# 1-Schematic_Lauflicht_28.net
KiCad netlist of a schematic drawn in EasyEDA
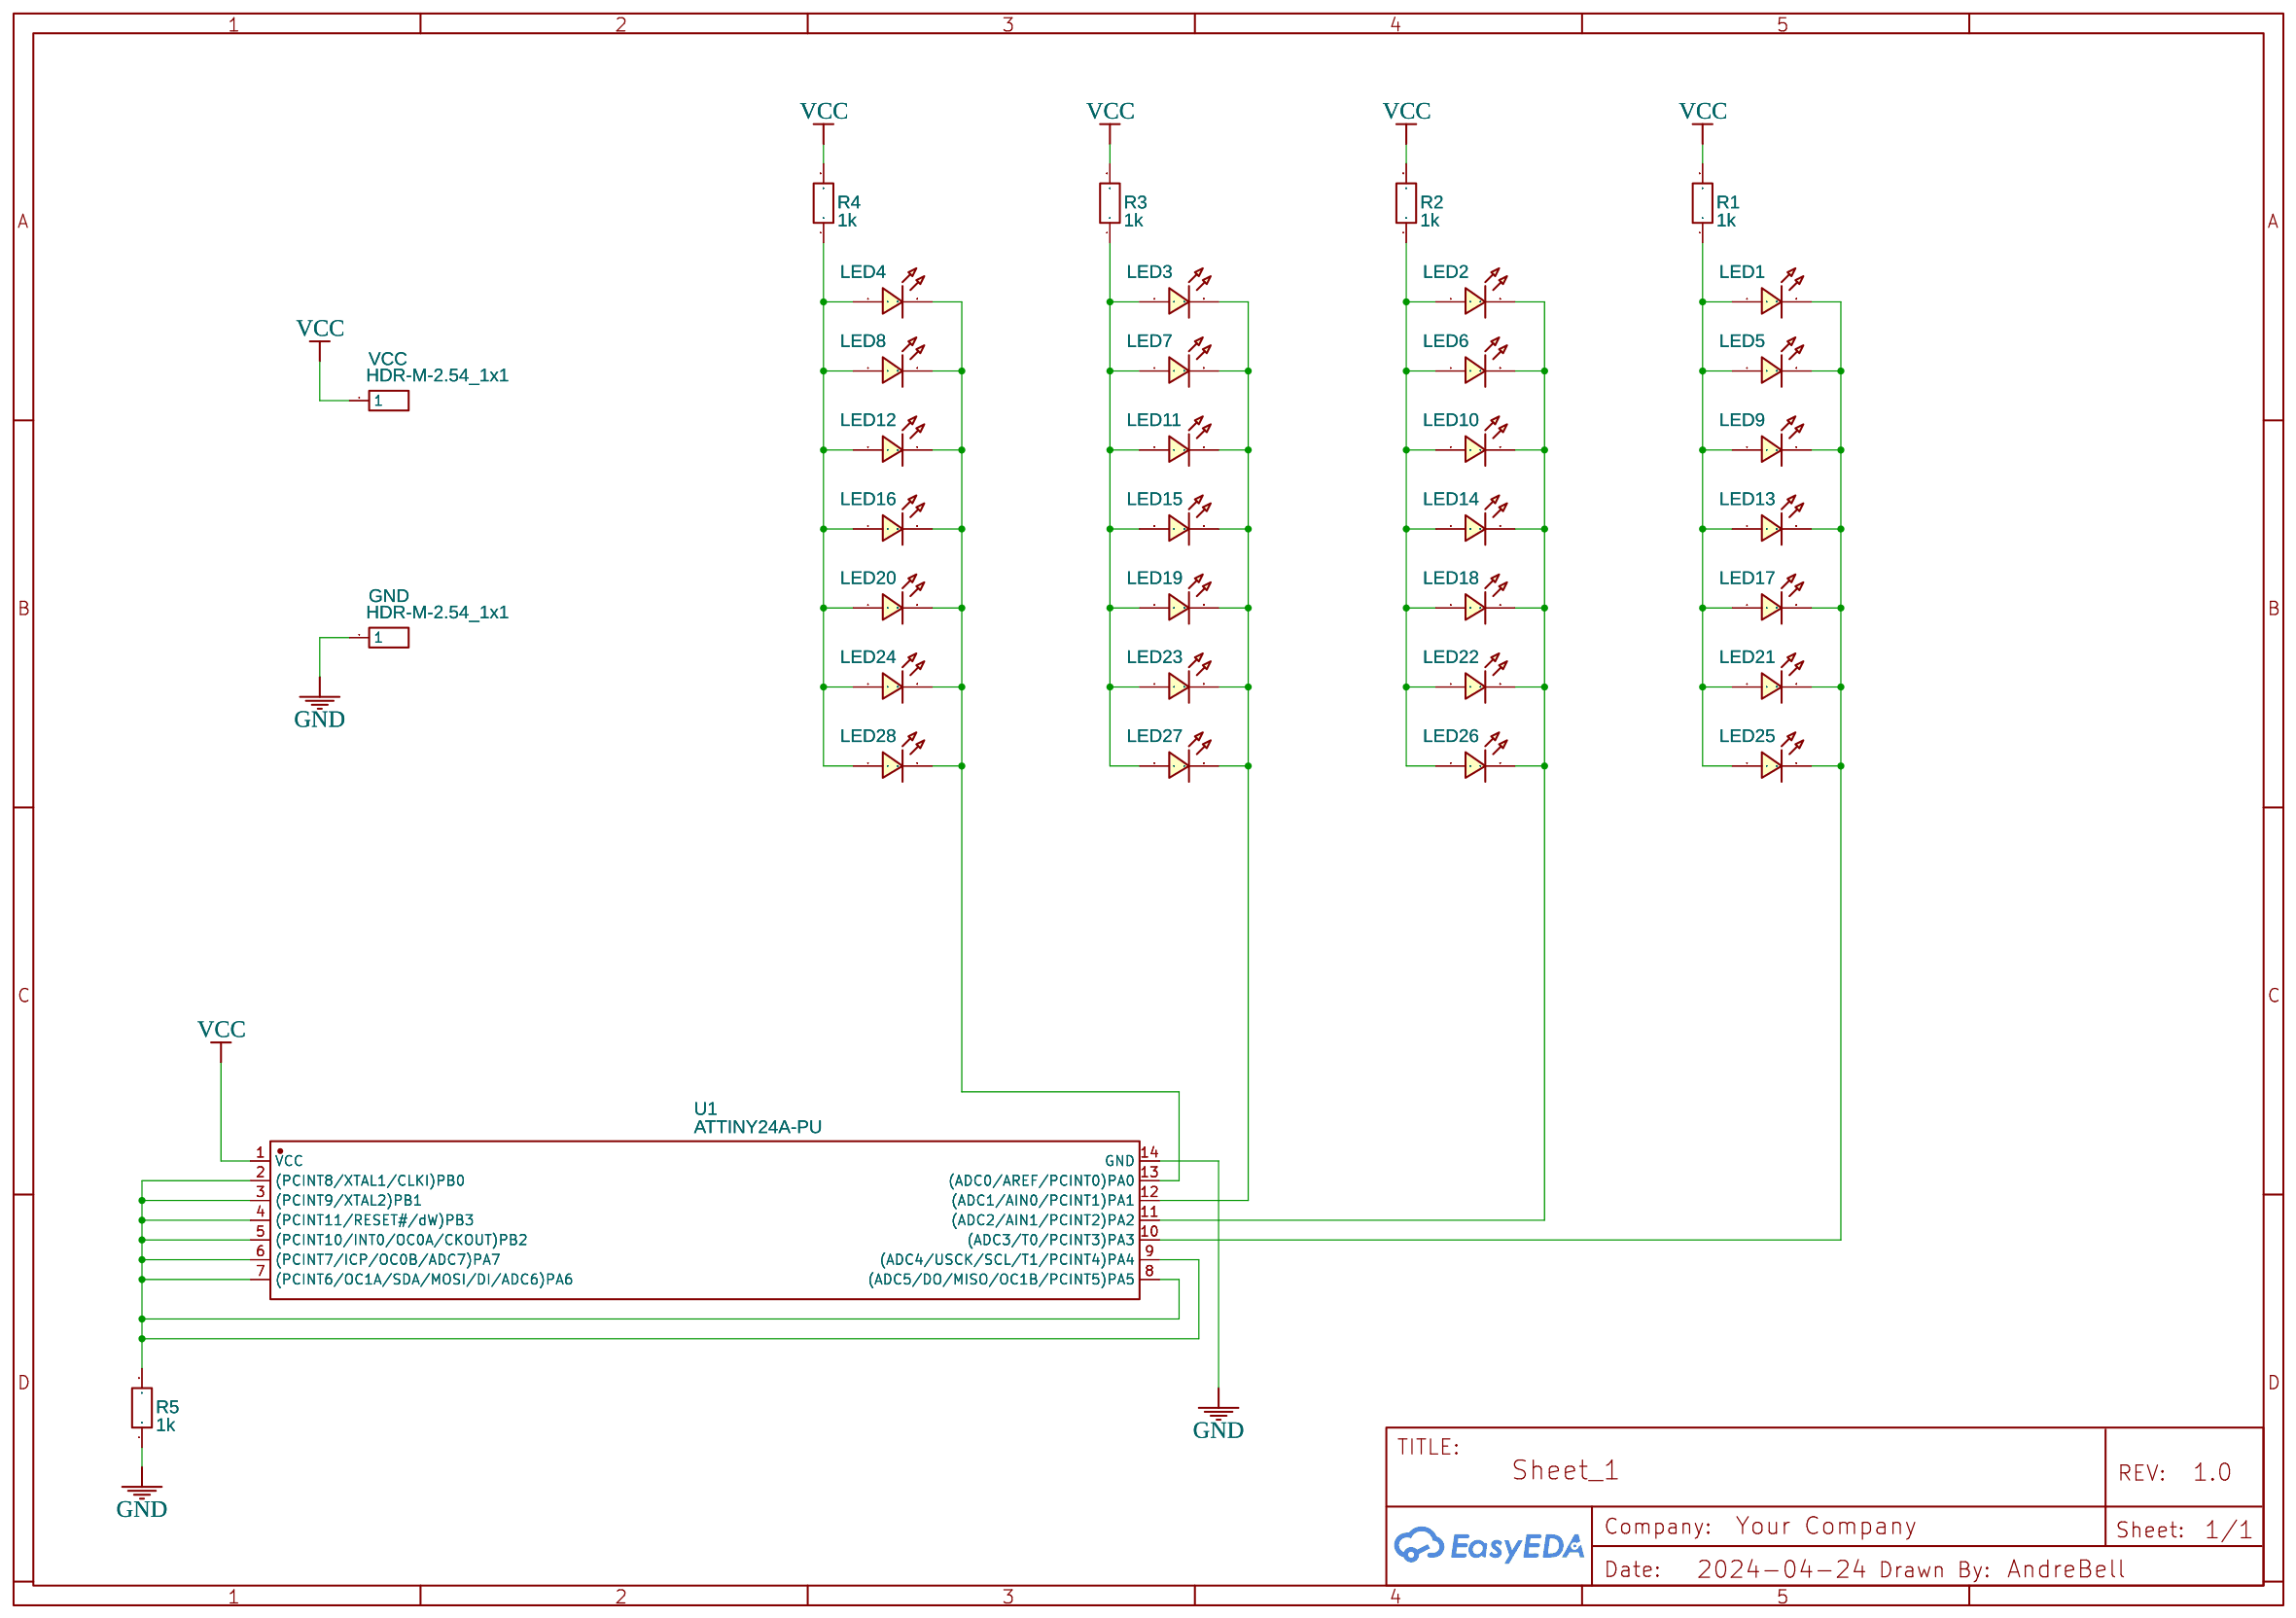
[diagram p0: schematic sheet]

(export (version "E")
  (design (tool "Eeschema 10.0.6"))
  (components
    (comp (ref "GND") (value "HDR-M-2.54_1x1") (libsource (lib "") (part "HDR-M-2.54_1x1_1")))
    (comp (ref "LED1")
      (value "LED-TH-3mm_G")
      (fields
        (field (name "Manufacturer Part") "204-10SYGD/S530-E3")
        (field (name "Manufacturer") "EVERLIGHT(台湾亿光)")
      )
      (libsource (lib "") (part "LED-TH-3mm_G"))
    )
    (comp (ref "LED2")
      (value "LED-TH-3mm_G")
      (fields
        (field (name "Manufacturer Part") "204-10SYGD/S530-E3")
        (field (name "Manufacturer") "EVERLIGHT(台湾亿光)")
      )
      (libsource (lib "") (part "LED-TH-3mm_G"))
    )
    (comp (ref "LED3")
      (value "LED-TH-3mm_G")
      (fields
        (field (name "Manufacturer Part") "204-10SYGD/S530-E3")
        (field (name "Manufacturer") "EVERLIGHT(台湾亿光)")
      )
      (libsource (lib "") (part "LED-TH-3mm_G"))
    )
    (comp (ref "LED4")
      (value "LED-TH-3mm_G")
      (fields
        (field (name "Manufacturer Part") "204-10SYGD/S530-E3")
        (field (name "Manufacturer") "EVERLIGHT(台湾亿光)")
      )
      (libsource (lib "") (part "LED-TH-3mm_G"))
    )
    (comp (ref "LED5")
      (value "LED-TH-3mm_G")
      (fields
        (field (name "Manufacturer Part") "204-10SYGD/S530-E3")
        (field (name "Manufacturer") "EVERLIGHT(台湾亿光)")
      )
      (libsource (lib "") (part "LED-TH-3mm_G"))
    )
    (comp (ref "LED6")
      (value "LED-TH-3mm_G")
      (fields
        (field (name "Manufacturer Part") "204-10SYGD/S530-E3")
        (field (name "Manufacturer") "EVERLIGHT(台湾亿光)")
      )
      (libsource (lib "") (part "LED-TH-3mm_G"))
    )
    (comp (ref "LED7")
      (value "LED-TH-3mm_G")
      (fields
        (field (name "Manufacturer Part") "204-10SYGD/S530-E3")
        (field (name "Manufacturer") "EVERLIGHT(台湾亿光)")
      )
      (libsource (lib "") (part "LED-TH-3mm_G"))
    )
    (comp (ref "LED8")
      (value "LED-TH-3mm_G")
      (fields
        (field (name "Manufacturer Part") "204-10SYGD/S530-E3")
        (field (name "Manufacturer") "EVERLIGHT(台湾亿光)")
      )
      (libsource (lib "") (part "LED-TH-3mm_G"))
    )
    (comp (ref "LED9")
      (value "LED-TH-3mm_G")
      (fields
        (field (name "Manufacturer Part") "204-10SYGD/S530-E3")
        (field (name "Manufacturer") "EVERLIGHT(台湾亿光)")
      )
      (libsource (lib "") (part "LED-TH-3mm_G"))
    )
    (comp (ref "LED10")
      (value "LED-TH-3mm_G")
      (fields
        (field (name "Manufacturer Part") "204-10SYGD/S530-E3")
        (field (name "Manufacturer") "EVERLIGHT(台湾亿光)")
      )
      (libsource (lib "") (part "LED-TH-3mm_G"))
    )
    (comp (ref "LED11")
      (value "LED-TH-3mm_G")
      (fields
        (field (name "Manufacturer Part") "204-10SYGD/S530-E3")
        (field (name "Manufacturer") "EVERLIGHT(台湾亿光)")
      )
      (libsource (lib "") (part "LED-TH-3mm_G"))
    )
    (comp (ref "LED12")
      (value "LED-TH-3mm_G")
      (fields
        (field (name "Manufacturer Part") "204-10SYGD/S530-E3")
        (field (name "Manufacturer") "EVERLIGHT(台湾亿光)")
      )
      (libsource (lib "") (part "LED-TH-3mm_G"))
    )
    (comp (ref "LED13")
      (value "LED-TH-3mm_G")
      (fields
        (field (name "Manufacturer Part") "204-10SYGD/S530-E3")
        (field (name "Manufacturer") "EVERLIGHT(台湾亿光)")
      )
      (libsource (lib "") (part "LED-TH-3mm_G"))
    )
    (comp (ref "LED14")
      (value "LED-TH-3mm_G")
      (fields
        (field (name "Manufacturer Part") "204-10SYGD/S530-E3")
        (field (name "Manufacturer") "EVERLIGHT(台湾亿光)")
      )
      (libsource (lib "") (part "LED-TH-3mm_G"))
    )
    (comp (ref "LED15")
      (value "LED-TH-3mm_G")
      (fields
        (field (name "Manufacturer Part") "204-10SYGD/S530-E3")
        (field (name "Manufacturer") "EVERLIGHT(台湾亿光)")
      )
      (libsource (lib "") (part "LED-TH-3mm_G"))
    )
    (comp (ref "LED16")
      (value "LED-TH-3mm_G")
      (fields
        (field (name "Manufacturer Part") "204-10SYGD/S530-E3")
        (field (name "Manufacturer") "EVERLIGHT(台湾亿光)")
      )
      (libsource (lib "") (part "LED-TH-3mm_G"))
    )
    (comp (ref "LED17")
      (value "LED-TH-3mm_G")
      (fields
        (field (name "Manufacturer Part") "204-10SYGD/S530-E3")
        (field (name "Manufacturer") "EVERLIGHT(台湾亿光)")
      )
      (libsource (lib "") (part "LED-TH-3mm_G"))
    )
    (comp (ref "LED18")
      (value "LED-TH-3mm_G")
      (fields
        (field (name "Manufacturer Part") "204-10SYGD/S530-E3")
        (field (name "Manufacturer") "EVERLIGHT(台湾亿光)")
      )
      (libsource (lib "") (part "LED-TH-3mm_G"))
    )
    (comp (ref "LED19")
      (value "LED-TH-3mm_G")
      (fields
        (field (name "Manufacturer Part") "204-10SYGD/S530-E3")
        (field (name "Manufacturer") "EVERLIGHT(台湾亿光)")
      )
      (libsource (lib "") (part "LED-TH-3mm_G"))
    )
    (comp (ref "LED20")
      (value "LED-TH-3mm_G")
      (fields
        (field (name "Manufacturer Part") "204-10SYGD/S530-E3")
        (field (name "Manufacturer") "EVERLIGHT(台湾亿光)")
      )
      (libsource (lib "") (part "LED-TH-3mm_G"))
    )
    (comp (ref "LED21")
      (value "LED-TH-3mm_G")
      (fields
        (field (name "Manufacturer Part") "204-10SYGD/S530-E3")
        (field (name "Manufacturer") "EVERLIGHT(台湾亿光)")
      )
      (libsource (lib "") (part "LED-TH-3mm_G"))
    )
    (comp (ref "LED22")
      (value "LED-TH-3mm_G")
      (fields
        (field (name "Manufacturer Part") "204-10SYGD/S530-E3")
        (field (name "Manufacturer") "EVERLIGHT(台湾亿光)")
      )
      (libsource (lib "") (part "LED-TH-3mm_G"))
    )
    (comp (ref "LED23")
      (value "LED-TH-3mm_G")
      (fields
        (field (name "Manufacturer Part") "204-10SYGD/S530-E3")
        (field (name "Manufacturer") "EVERLIGHT(台湾亿光)")
      )
      (libsource (lib "") (part "LED-TH-3mm_G"))
    )
    (comp (ref "LED24")
      (value "LED-TH-3mm_G")
      (fields
        (field (name "Manufacturer Part") "204-10SYGD/S530-E3")
        (field (name "Manufacturer") "EVERLIGHT(台湾亿光)")
      )
      (libsource (lib "") (part "LED-TH-3mm_G"))
    )
    (comp (ref "LED25")
      (value "LED-TH-3mm_G")
      (fields
        (field (name "Manufacturer Part") "204-10SYGD/S530-E3")
        (field (name "Manufacturer") "EVERLIGHT(台湾亿光)")
      )
      (libsource (lib "") (part "LED-TH-3mm_G"))
    )
    (comp (ref "LED26")
      (value "LED-TH-3mm_G")
      (fields
        (field (name "Manufacturer Part") "204-10SYGD/S530-E3")
        (field (name "Manufacturer") "EVERLIGHT(台湾亿光)")
      )
      (libsource (lib "") (part "LED-TH-3mm_G"))
    )
    (comp (ref "LED27")
      (value "LED-TH-3mm_G")
      (fields
        (field (name "Manufacturer Part") "204-10SYGD/S530-E3")
        (field (name "Manufacturer") "EVERLIGHT(台湾亿光)")
      )
      (libsource (lib "") (part "LED-TH-3mm_G"))
    )
    (comp (ref "LED28")
      (value "LED-TH-3mm_G")
      (fields
        (field (name "Manufacturer Part") "204-10SYGD/S530-E3")
        (field (name "Manufacturer") "EVERLIGHT(台湾亿光)")
      )
      (libsource (lib "") (part "LED-TH-3mm_G"))
    )
    (comp (ref "R1") (value "1k") (libsource (lib "") (part "R_AXIAL-0.3_EU")))
    (comp (ref "R2") (value "1k") (libsource (lib "") (part "R_AXIAL-0.3_EU")))
    (comp (ref "R3") (value "1k") (libsource (lib "") (part "R_AXIAL-0.3_EU")))
    (comp (ref "R4") (value "1k") (libsource (lib "") (part "R_AXIAL-0.3_EU")))
    (comp (ref "R5") (value "1k") (libsource (lib "") (part "R_AXIAL-0.3_EU")))
    (comp (ref "U1")
      (value "ATTINY24A-PU")
      (fields (field (name "Manufacturer") "MICROCHIP(美国微芯)"))
      (libsource (lib "") (part "ATTINY24A-PU"))
    )
    (comp (ref "VCC") (value "HDR-M-2.54_1x1") (libsource (lib "") (part "HDR-M-2.54_1x1")))
  )
  (nets
    (net (code "1") (name "GND") (class "Default")
      (node (ref "GND") (pin "1") (pinfunction "1_1") (pintype "input"))
      (node (ref "R5") (pin "1") (pinfunction "1_1") (pintype "unspecified"))
      (node (ref "U1") (pin "14") (pinfunction "GND_14") (pintype "unspecified"))
    )
    (net (code "2") (name "Net-(LED1-Pad1)") (class "Default")
      (node (ref "LED1") (pin "1") (pinfunction "1_1") (pintype "unspecified"))
      (node (ref "LED13") (pin "1") (pinfunction "1_1") (pintype "unspecified"))
      (node (ref "LED17") (pin "1") (pinfunction "1_1") (pintype "unspecified"))
      (node (ref "LED21") (pin "1") (pinfunction "1_1") (pintype "unspecified"))
      (node (ref "LED25") (pin "1") (pinfunction "1_1") (pintype "unspecified"))
      (node (ref "LED5") (pin "1") (pinfunction "1_1") (pintype "unspecified"))
      (node (ref "LED9") (pin "1") (pinfunction "1_1") (pintype "unspecified"))
      (node (ref "R1") (pin "1") (pinfunction "1_1") (pintype "unspecified"))
    )
    (net (code "3") (name "Net-(LED10-Pad1)") (class "Default")
      (node (ref "LED10") (pin "1") (pinfunction "1_1") (pintype "unspecified"))
      (node (ref "LED14") (pin "1") (pinfunction "1_1") (pintype "unspecified"))
      (node (ref "LED18") (pin "1") (pinfunction "1_1") (pintype "unspecified"))
      (node (ref "LED2") (pin "1") (pinfunction "1_1") (pintype "unspecified"))
      (node (ref "LED22") (pin "1") (pinfunction "1_1") (pintype "unspecified"))
      (node (ref "LED26") (pin "1") (pinfunction "1_1") (pintype "unspecified"))
      (node (ref "LED6") (pin "1") (pinfunction "1_1") (pintype "unspecified"))
      (node (ref "R2") (pin "1") (pinfunction "1_1") (pintype "unspecified"))
    )
    (net (code "4") (name "Net-(LED11-Pad1)") (class "Default")
      (node (ref "LED11") (pin "1") (pinfunction "1_1") (pintype "unspecified"))
      (node (ref "LED15") (pin "1") (pinfunction "1_1") (pintype "unspecified"))
      (node (ref "LED19") (pin "1") (pinfunction "1_1") (pintype "unspecified"))
      (node (ref "LED23") (pin "1") (pinfunction "1_1") (pintype "unspecified"))
      (node (ref "LED27") (pin "1") (pinfunction "1_1") (pintype "unspecified"))
      (node (ref "LED3") (pin "1") (pinfunction "1_1") (pintype "unspecified"))
      (node (ref "LED7") (pin "1") (pinfunction "1_1") (pintype "unspecified"))
      (node (ref "R3") (pin "1") (pinfunction "1_1") (pintype "unspecified"))
    )
    (net (code "5") (name "Net-(LED12-Pad1)") (class "Default")
      (node (ref "LED12") (pin "1") (pinfunction "1_1") (pintype "unspecified"))
      (node (ref "LED16") (pin "1") (pinfunction "1_1") (pintype "unspecified"))
      (node (ref "LED20") (pin "1") (pinfunction "1_1") (pintype "unspecified"))
      (node (ref "LED24") (pin "1") (pinfunction "1_1") (pintype "unspecified"))
      (node (ref "LED28") (pin "1") (pinfunction "1_1") (pintype "unspecified"))
      (node (ref "LED4") (pin "1") (pinfunction "1_1") (pintype "unspecified"))
      (node (ref "LED8") (pin "1") (pinfunction "1_1") (pintype "unspecified"))
      (node (ref "R4") (pin "1") (pinfunction "1_1") (pintype "unspecified"))
    )
    (net (code "6") (name "Net-(U1-(ADC0{slash}AREF{slash}PCINT0)PA0)") (class "Default")
      (node (ref "LED12") (pin "2") (pinfunction "2_2") (pintype "unspecified"))
      (node (ref "LED16") (pin "2") (pinfunction "2_2") (pintype "unspecified"))
      (node (ref "LED20") (pin "2") (pinfunction "2_2") (pintype "unspecified"))
      (node (ref "LED24") (pin "2") (pinfunction "2_2") (pintype "unspecified"))
      (node (ref "LED28") (pin "2") (pinfunction "2_2") (pintype "unspecified"))
      (node (ref "LED4") (pin "2") (pinfunction "2_2") (pintype "unspecified"))
      (node (ref "LED8") (pin "2") (pinfunction "2_2") (pintype "unspecified"))
      (node (ref "U1") (pin "13") (pinfunction "(ADC0/AREF/PCINT0)PA0_13") (pintype "unspecified"))
    )
    (net (code "7") (name "Net-(U1-(ADC1{slash}AIN0{slash}PCINT1)PA1)") (class "Default")
      (node (ref "LED11") (pin "2") (pinfunction "2_2") (pintype "unspecified"))
      (node (ref "LED15") (pin "2") (pinfunction "2_2") (pintype "unspecified"))
      (node (ref "LED19") (pin "2") (pinfunction "2_2") (pintype "unspecified"))
      (node (ref "LED23") (pin "2") (pinfunction "2_2") (pintype "unspecified"))
      (node (ref "LED27") (pin "2") (pinfunction "2_2") (pintype "unspecified"))
      (node (ref "LED3") (pin "2") (pinfunction "2_2") (pintype "unspecified"))
      (node (ref "LED7") (pin "2") (pinfunction "2_2") (pintype "unspecified"))
      (node (ref "U1") (pin "12") (pinfunction "(ADC1/AIN0/PCINT1)PA1_12") (pintype "unspecified"))
    )
    (net (code "8") (name "Net-(U1-(ADC2{slash}AIN1{slash}PCINT2)PA2)") (class "Default")
      (node (ref "LED10") (pin "2") (pinfunction "2_2") (pintype "unspecified"))
      (node (ref "LED14") (pin "2") (pinfunction "2_2") (pintype "unspecified"))
      (node (ref "LED18") (pin "2") (pinfunction "2_2") (pintype "unspecified"))
      (node (ref "LED2") (pin "2") (pinfunction "2_2") (pintype "unspecified"))
      (node (ref "LED22") (pin "2") (pinfunction "2_2") (pintype "unspecified"))
      (node (ref "LED26") (pin "2") (pinfunction "2_2") (pintype "unspecified"))
      (node (ref "LED6") (pin "2") (pinfunction "2_2") (pintype "unspecified"))
      (node (ref "U1") (pin "11") (pinfunction "(ADC2/AIN1/PCINT2)PA2_11") (pintype "unspecified"))
    )
    (net (code "9") (name "Net-(U1-(ADC3{slash}T0{slash}PCINT3)PA3)") (class "Default")
      (node (ref "LED1") (pin "2") (pinfunction "2_2") (pintype "unspecified"))
      (node (ref "LED13") (pin "2") (pinfunction "2_2") (pintype "unspecified"))
      (node (ref "LED17") (pin "2") (pinfunction "2_2") (pintype "unspecified"))
      (node (ref "LED21") (pin "2") (pinfunction "2_2") (pintype "unspecified"))
      (node (ref "LED25") (pin "2") (pinfunction "2_2") (pintype "unspecified"))
      (node (ref "LED5") (pin "2") (pinfunction "2_2") (pintype "unspecified"))
      (node (ref "LED9") (pin "2") (pinfunction "2_2") (pintype "unspecified"))
      (node (ref "U1") (pin "10") (pinfunction "(ADC3/T0/PCINT3)PA3_10") (pintype "unspecified"))
    )
    (net (code "10") (name "Net-(U1-(ADC4{slash}USCK{slash}SCL{slash}T1{slash}PCINT4)PA4)") (class "Default")
      (node (ref "R5") (pin "2") (pinfunction "2_2") (pintype "unspecified"))
      (node (ref "U1") (pin "2") (pinfunction "(PCINT8/XTAL1/CLKI)PB0_2") (pintype "unspecified"))
      (node (ref "U1") (pin "3") (pinfunction "(PCINT9/XTAL2)PB1_3") (pintype "unspecified"))
      (node (ref "U1") (pin "4") (pinfunction "(PCINT11/RESET#/dW)PB3_4") (pintype "unspecified"))
      (node (ref "U1") (pin "5") (pinfunction "(PCINT10/INT0/OC0A/CKOUT)PB2_5") (pintype "unspecified"))
      (node (ref "U1") (pin "6") (pinfunction "(PCINT7/ICP/OC0B/ADC7)PA7_6") (pintype "unspecified"))
      (node (ref "U1") (pin "7") (pinfunction "(PCINT6/OC1A/SDA/MOSI/DI/ADC6)PA6_7") (pintype "unspecified"))
      (node (ref "U1") (pin "8") (pinfunction "(ADC5/DO/MISO/OC1B/PCINT5)PA5_8") (pintype "unspecified"))
      (node (ref "U1") (pin "9") (pinfunction "(ADC4/USCK/SCL/T1/PCINT4)PA4_9") (pintype "unspecified"))
    )
    (net (code "11") (name "VCC") (class "Default")
      (node (ref "R1") (pin "2") (pinfunction "2_2") (pintype "unspecified"))
      (node (ref "R2") (pin "2") (pinfunction "2_2") (pintype "unspecified"))
      (node (ref "R3") (pin "2") (pinfunction "2_2") (pintype "unspecified"))
      (node (ref "R4") (pin "2") (pinfunction "2_2") (pintype "unspecified"))
      (node (ref "U1") (pin "1") (pinfunction "VCC_1") (pintype "unspecified"))
      (node (ref "VCC") (pin "1") (pinfunction "1_1") (pintype "input"))
    )
  )
)
